# cable_with_five_imu.net
KiCad netlist of a schematic drawn in EAGLE
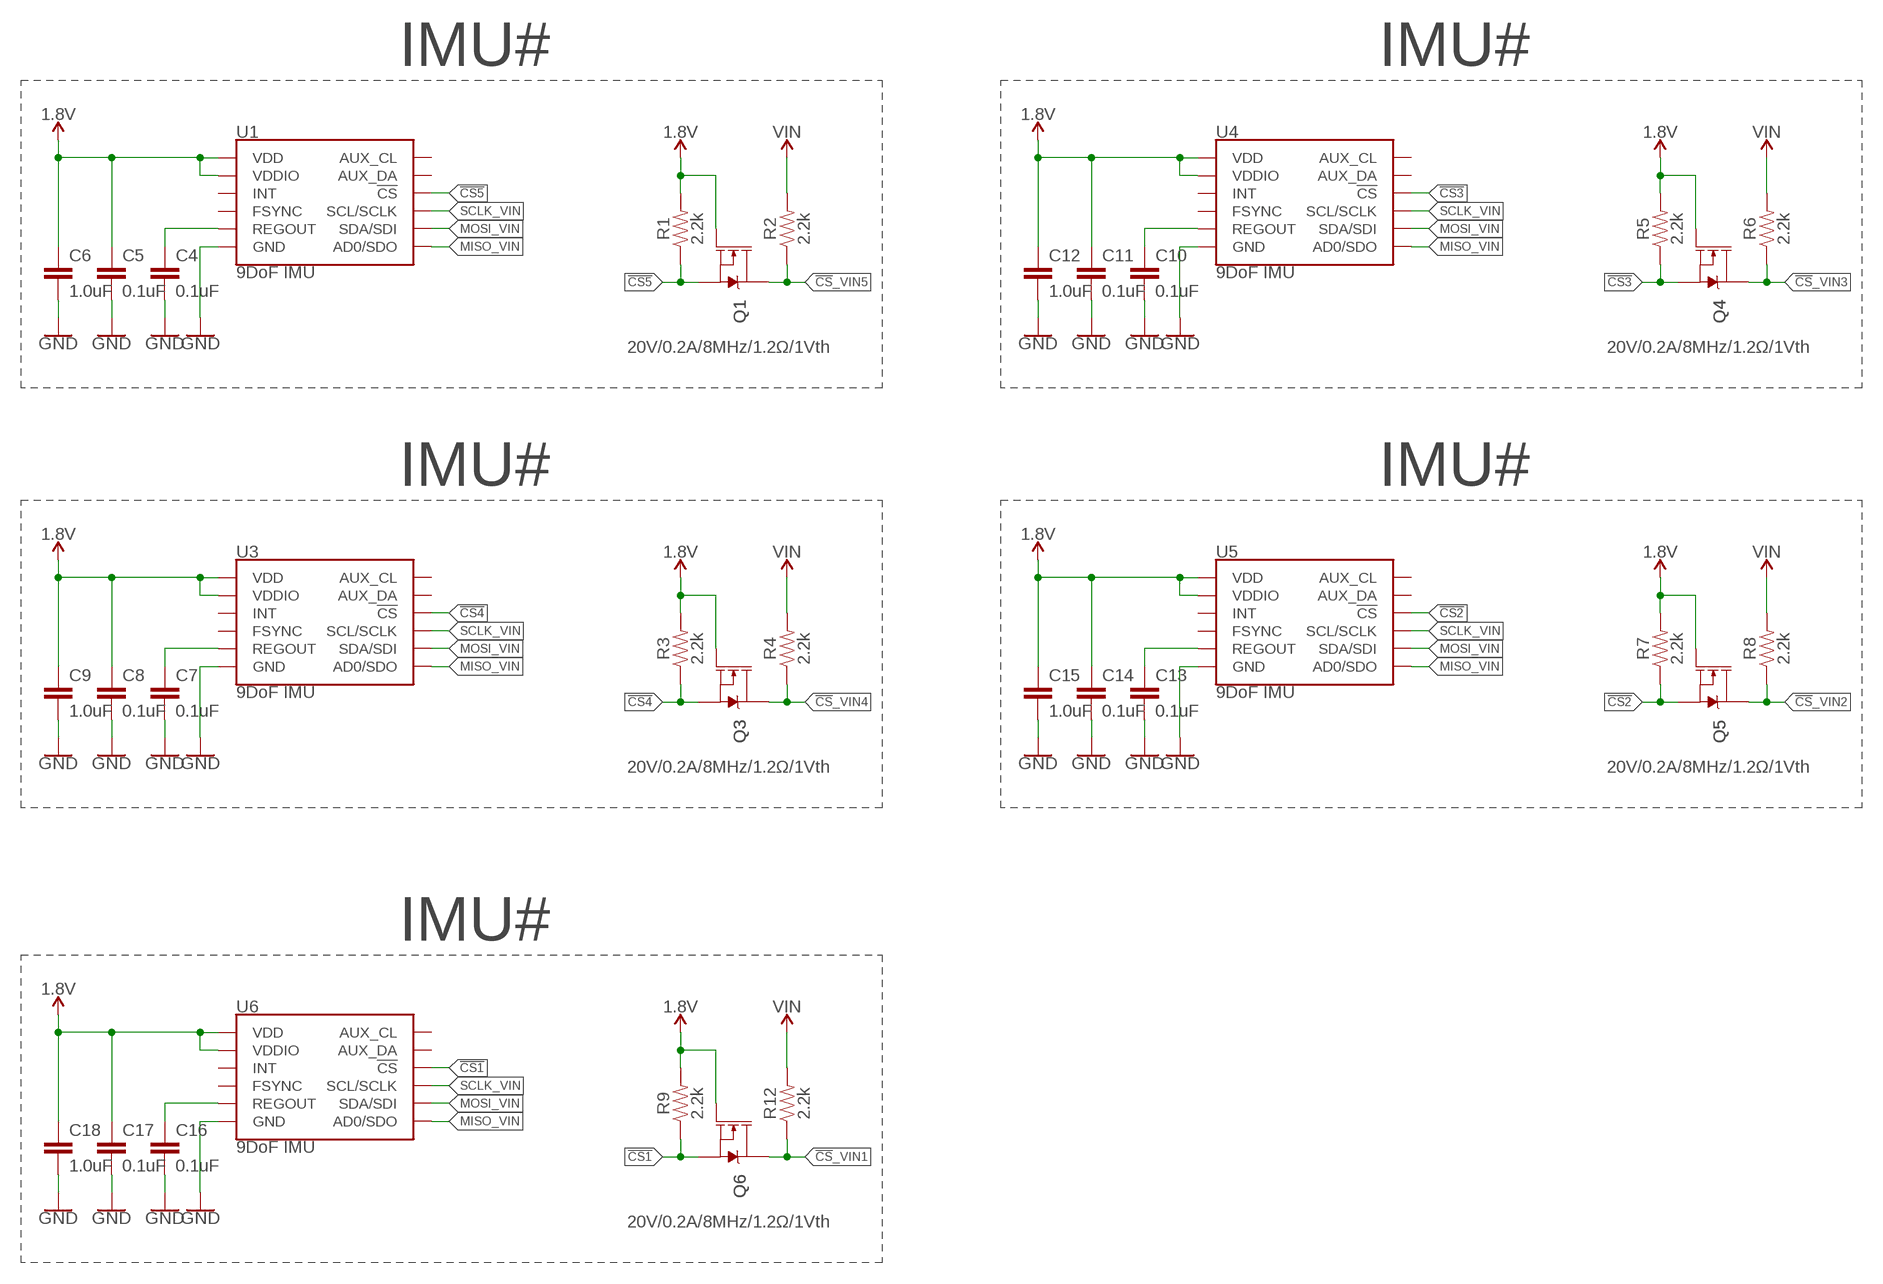
[diagram p0: schematic, sheet 1]

(export (version "E")
  (design (tool "Eeschema 10.0.6"))
  (components
    (comp (ref "C4")
      (value "0.1uF")
      (footprint "eagle-import:0603")
      (libsource (lib "eagle-import") (part "0.1UF-0603-25V-5%"))
    )
    (comp (ref "C5")
      (value "0.1uF")
      (footprint "eagle-import:0603")
      (libsource (lib "eagle-import") (part "0.1UF-0603-25V-5%"))
    )
    (comp (ref "C6")
      (value "1.0uF")
      (footprint "eagle-import:0603")
      (libsource (lib "eagle-import") (part "1.0UF-0603-16V-10%-X7R"))
    )
    (comp (ref "C7")
      (value "0.1uF")
      (footprint "eagle-import:0603")
      (libsource (lib "eagle-import") (part "0.1UF-0603-25V-5%"))
    )
    (comp (ref "C8")
      (value "0.1uF")
      (footprint "eagle-import:0603")
      (libsource (lib "eagle-import") (part "0.1UF-0603-25V-5%"))
    )
    (comp (ref "C9")
      (value "1.0uF")
      (footprint "eagle-import:0603")
      (libsource (lib "eagle-import") (part "1.0UF-0603-16V-10%-X7R"))
    )
    (comp (ref "C10")
      (value "0.1uF")
      (footprint "eagle-import:0603")
      (libsource (lib "eagle-import") (part "0.1UF-0603-25V-5%"))
    )
    (comp (ref "C11")
      (value "0.1uF")
      (footprint "eagle-import:0603")
      (libsource (lib "eagle-import") (part "0.1UF-0603-25V-5%"))
    )
    (comp (ref "C12")
      (value "1.0uF")
      (footprint "eagle-import:0603")
      (libsource (lib "eagle-import") (part "1.0UF-0603-16V-10%-X7R"))
    )
    (comp (ref "C13")
      (value "0.1uF")
      (footprint "eagle-import:0603")
      (libsource (lib "eagle-import") (part "0.1UF-0603-25V-5%"))
    )
    (comp (ref "C14")
      (value "0.1uF")
      (footprint "eagle-import:0603")
      (libsource (lib "eagle-import") (part "0.1UF-0603-25V-5%"))
    )
    (comp (ref "C15")
      (value "1.0uF")
      (footprint "eagle-import:0603")
      (libsource (lib "eagle-import") (part "1.0UF-0603-16V-10%-X7R"))
    )
    (comp (ref "C16")
      (value "0.1uF")
      (footprint "eagle-import:0603")
      (libsource (lib "eagle-import") (part "0.1UF-0603-25V-5%"))
    )
    (comp (ref "C17")
      (value "0.1uF")
      (footprint "eagle-import:0603")
      (libsource (lib "eagle-import") (part "0.1UF-0603-25V-5%"))
    )
    (comp (ref "C18")
      (value "1.0uF")
      (footprint "eagle-import:0603")
      (libsource (lib "eagle-import") (part "1.0UF-0603-16V-10%-X7R"))
    )
    (comp (ref "Q1")
      (value "20V/0.2A/8MHz/1.2Ω/1Vth")
      (footprint "eagle-import:SOT-416FL")
      (libsource (lib "eagle-import") (part "MOSFET-NCH-RE1C002UN"))
    )
    (comp (ref "Q3")
      (value "20V/0.2A/8MHz/1.2Ω/1Vth")
      (footprint "eagle-import:SOT-416FL")
      (libsource (lib "eagle-import") (part "MOSFET-NCH-RE1C002UN"))
    )
    (comp (ref "Q4")
      (value "20V/0.2A/8MHz/1.2Ω/1Vth")
      (footprint "eagle-import:SOT-416FL")
      (libsource (lib "eagle-import") (part "MOSFET-NCH-RE1C002UN"))
    )
    (comp (ref "Q5")
      (value "20V/0.2A/8MHz/1.2Ω/1Vth")
      (footprint "eagle-import:SOT-416FL")
      (libsource (lib "eagle-import") (part "MOSFET-NCH-RE1C002UN"))
    )
    (comp (ref "Q6")
      (value "20V/0.2A/8MHz/1.2Ω/1Vth")
      (footprint "eagle-import:SOT-416FL")
      (libsource (lib "eagle-import") (part "MOSFET-NCH-RE1C002UN"))
    )
    (comp (ref "R1")
      (value "2.2k")
      (footprint "eagle-import:0402-TIGHT")
      (libsource (lib "eagle-import") (part "2.2KOHM-0402T-1/16W-1%"))
    )
    (comp (ref "R2")
      (value "2.2k")
      (footprint "eagle-import:0402-TIGHT")
      (libsource (lib "eagle-import") (part "2.2KOHM-0402T-1/16W-1%"))
    )
    (comp (ref "R3")
      (value "2.2k")
      (footprint "eagle-import:0402-TIGHT")
      (libsource (lib "eagle-import") (part "2.2KOHM-0402T-1/16W-1%"))
    )
    (comp (ref "R4")
      (value "2.2k")
      (footprint "eagle-import:0402-TIGHT")
      (libsource (lib "eagle-import") (part "2.2KOHM-0402T-1/16W-1%"))
    )
    (comp (ref "R5")
      (value "2.2k")
      (footprint "eagle-import:0402-TIGHT")
      (libsource (lib "eagle-import") (part "2.2KOHM-0402T-1/16W-1%"))
    )
    (comp (ref "R6")
      (value "2.2k")
      (footprint "eagle-import:0402-TIGHT")
      (libsource (lib "eagle-import") (part "2.2KOHM-0402T-1/16W-1%"))
    )
    (comp (ref "R7")
      (value "2.2k")
      (footprint "eagle-import:0402-TIGHT")
      (libsource (lib "eagle-import") (part "2.2KOHM-0402T-1/16W-1%"))
    )
    (comp (ref "R8")
      (value "2.2k")
      (footprint "eagle-import:0402-TIGHT")
      (libsource (lib "eagle-import") (part "2.2KOHM-0402T-1/16W-1%"))
    )
    (comp (ref "R9")
      (value "2.2k")
      (footprint "eagle-import:0402-TIGHT")
      (libsource (lib "eagle-import") (part "2.2KOHM-0402T-1/16W-1%"))
    )
    (comp (ref "R12")
      (value "2.2k")
      (footprint "eagle-import:0402-TIGHT")
      (libsource (lib "eagle-import") (part "2.2KOHM-0402T-1/16W-1%"))
    )
    (comp (ref "U1")
      (value "9DoF IMU")
      (footprint "eagle-import:QFN24-3X3")
      (libsource (lib "eagle-import") (part "ICM-20948"))
    )
    (comp (ref "U3")
      (value "9DoF IMU")
      (footprint "eagle-import:QFN24-3X3")
      (libsource (lib "eagle-import") (part "ICM-20948"))
    )
    (comp (ref "U4")
      (value "9DoF IMU")
      (footprint "eagle-import:QFN24-3X3")
      (libsource (lib "eagle-import") (part "ICM-20948"))
    )
    (comp (ref "U5")
      (value "9DoF IMU")
      (footprint "eagle-import:QFN24-3X3")
      (libsource (lib "eagle-import") (part "ICM-20948"))
    )
    (comp (ref "U6")
      (value "9DoF IMU")
      (footprint "eagle-import:QFN24-3X3")
      (libsource (lib "eagle-import") (part "ICM-20948"))
    )
  )
  (nets
    (net (code "1") (name "/~{CS1}") (class "Default")
      (node (ref "Q6") (pin "2") (pinfunction "S_2") (pintype "bidirectional"))
      (node (ref "R9") (pin "1") (pinfunction "1_1") (pintype "passive"))
      (node (ref "U6") (pin "22") (pinfunction "~{CS}_22") (pintype "bidirectional"))
    )
    (net (code "2") (name "/~{CS2}") (class "Default")
      (node (ref "Q5") (pin "2") (pinfunction "S_2") (pintype "bidirectional"))
      (node (ref "R7") (pin "1") (pinfunction "1_1") (pintype "passive"))
      (node (ref "U5") (pin "22") (pinfunction "~{CS}_22") (pintype "bidirectional"))
    )
    (net (code "3") (name "/~{CS3}") (class "Default")
      (node (ref "Q4") (pin "2") (pinfunction "S_2") (pintype "bidirectional"))
      (node (ref "R5") (pin "1") (pinfunction "1_1") (pintype "passive"))
      (node (ref "U4") (pin "22") (pinfunction "~{CS}_22") (pintype "bidirectional"))
    )
    (net (code "4") (name "/~{CS4}") (class "Default")
      (node (ref "Q3") (pin "2") (pinfunction "S_2") (pintype "bidirectional"))
      (node (ref "R3") (pin "1") (pinfunction "1_1") (pintype "passive"))
      (node (ref "U3") (pin "22") (pinfunction "~{CS}_22") (pintype "bidirectional"))
    )
    (net (code "5") (name "/~{CS5}") (class "Default")
      (node (ref "Q1") (pin "2") (pinfunction "S_2") (pintype "bidirectional"))
      (node (ref "R1") (pin "1") (pinfunction "1_1") (pintype "passive"))
      (node (ref "U1") (pin "22") (pinfunction "~{CS}_22") (pintype "bidirectional"))
    )
    (net (code "6") (name "/~{CS}_VIN1") (class "Default")
      (node (ref "Q6") (pin "3") (pinfunction "D_3") (pintype "bidirectional"))
      (node (ref "R12") (pin "1") (pinfunction "1_1") (pintype "passive"))
    )
    (net (code "7") (name "/~{CS}_VIN2") (class "Default")
      (node (ref "Q5") (pin "3") (pinfunction "D_3") (pintype "bidirectional"))
      (node (ref "R8") (pin "1") (pinfunction "1_1") (pintype "passive"))
    )
    (net (code "8") (name "/~{CS}_VIN3") (class "Default")
      (node (ref "Q4") (pin "3") (pinfunction "D_3") (pintype "bidirectional"))
      (node (ref "R6") (pin "1") (pinfunction "1_1") (pintype "passive"))
    )
    (net (code "9") (name "/~{CS}_VIN4") (class "Default")
      (node (ref "Q3") (pin "3") (pinfunction "D_3") (pintype "bidirectional"))
      (node (ref "R4") (pin "1") (pinfunction "1_1") (pintype "passive"))
    )
    (net (code "10") (name "/~{CS}_VIN5") (class "Default")
      (node (ref "Q1") (pin "3") (pinfunction "D_3") (pintype "bidirectional"))
      (node (ref "R2") (pin "1") (pinfunction "1_1") (pintype "passive"))
    )
    (net (code "11") (name "1.8V") (class "Default")
      (node (ref "C11") (pin "1") (pinfunction "1_1") (pintype "passive"))
      (node (ref "C12") (pin "1") (pinfunction "1_1") (pintype "passive"))
      (node (ref "C14") (pin "1") (pinfunction "1_1") (pintype "passive"))
      (node (ref "C15") (pin "1") (pinfunction "1_1") (pintype "passive"))
      (node (ref "C17") (pin "1") (pinfunction "1_1") (pintype "passive"))
      (node (ref "C18") (pin "1") (pinfunction "1_1") (pintype "passive"))
      (node (ref "C5") (pin "1") (pinfunction "1_1") (pintype "passive"))
      (node (ref "C6") (pin "1") (pinfunction "1_1") (pintype "passive"))
      (node (ref "C8") (pin "1") (pinfunction "1_1") (pintype "passive"))
      (node (ref "C9") (pin "1") (pinfunction "1_1") (pintype "passive"))
      (node (ref "Q1") (pin "1") (pinfunction "G_1") (pintype "bidirectional"))
      (node (ref "Q3") (pin "1") (pinfunction "G_1") (pintype "bidirectional"))
      (node (ref "Q4") (pin "1") (pinfunction "G_1") (pintype "bidirectional"))
      (node (ref "Q5") (pin "1") (pinfunction "G_1") (pintype "bidirectional"))
      (node (ref "Q6") (pin "1") (pinfunction "G_1") (pintype "bidirectional"))
      (node (ref "R1") (pin "2") (pinfunction "2_2") (pintype "passive"))
      (node (ref "R3") (pin "2") (pinfunction "2_2") (pintype "passive"))
      (node (ref "R5") (pin "2") (pinfunction "2_2") (pintype "passive"))
      (node (ref "R7") (pin "2") (pinfunction "2_2") (pintype "passive"))
      (node (ref "R9") (pin "2") (pinfunction "2_2") (pintype "passive"))
      (node (ref "U1") (pin "13") (pinfunction "VDD_13") (pintype "bidirectional"))
      (node (ref "U1") (pin "8") (pinfunction "VDDIO_8") (pintype "bidirectional"))
      (node (ref "U3") (pin "13") (pinfunction "VDD_13") (pintype "bidirectional"))
      (node (ref "U3") (pin "8") (pinfunction "VDDIO_8") (pintype "bidirectional"))
      (node (ref "U4") (pin "13") (pinfunction "VDD_13") (pintype "bidirectional"))
      (node (ref "U4") (pin "8") (pinfunction "VDDIO_8") (pintype "bidirectional"))
      (node (ref "U5") (pin "13") (pinfunction "VDD_13") (pintype "bidirectional"))
      (node (ref "U5") (pin "8") (pinfunction "VDDIO_8") (pintype "bidirectional"))
      (node (ref "U6") (pin "13") (pinfunction "VDD_13") (pintype "bidirectional"))
      (node (ref "U6") (pin "8") (pinfunction "VDDIO_8") (pintype "bidirectional"))
    )
    (net (code "12") (name "GND") (class "Default")
      (node (ref "C10") (pin "2") (pinfunction "2_2") (pintype "passive"))
      (node (ref "C11") (pin "2") (pinfunction "2_2") (pintype "passive"))
      (node (ref "C12") (pin "2") (pinfunction "2_2") (pintype "passive"))
      (node (ref "C13") (pin "2") (pinfunction "2_2") (pintype "passive"))
      (node (ref "C14") (pin "2") (pinfunction "2_2") (pintype "passive"))
      (node (ref "C15") (pin "2") (pinfunction "2_2") (pintype "passive"))
      (node (ref "C16") (pin "2") (pinfunction "2_2") (pintype "passive"))
      (node (ref "C17") (pin "2") (pinfunction "2_2") (pintype "passive"))
      (node (ref "C18") (pin "2") (pinfunction "2_2") (pintype "passive"))
      (node (ref "C4") (pin "2") (pinfunction "2_2") (pintype "passive"))
      (node (ref "C5") (pin "2") (pinfunction "2_2") (pintype "passive"))
      (node (ref "C6") (pin "2") (pinfunction "2_2") (pintype "passive"))
      (node (ref "C7") (pin "2") (pinfunction "2_2") (pintype "passive"))
      (node (ref "C8") (pin "2") (pinfunction "2_2") (pintype "passive"))
      (node (ref "C9") (pin "2") (pinfunction "2_2") (pintype "passive"))
      (node (ref "U1") (pin "18") (pinfunction "GND_18") (pintype "bidirectional"))
      (node (ref "U1") (pin "20") (pinfunction "GND_20") (pintype "bidirectional"))
      (node (ref "U3") (pin "18") (pinfunction "GND_18") (pintype "bidirectional"))
      (node (ref "U3") (pin "20") (pinfunction "GND_20") (pintype "bidirectional"))
      (node (ref "U4") (pin "18") (pinfunction "GND_18") (pintype "bidirectional"))
      (node (ref "U4") (pin "20") (pinfunction "GND_20") (pintype "bidirectional"))
      (node (ref "U5") (pin "18") (pinfunction "GND_18") (pintype "bidirectional"))
      (node (ref "U5") (pin "20") (pinfunction "GND_20") (pintype "bidirectional"))
      (node (ref "U6") (pin "18") (pinfunction "GND_18") (pintype "bidirectional"))
      (node (ref "U6") (pin "20") (pinfunction "GND_20") (pintype "bidirectional"))
    )
    (net (code "13") (name "MISO_VIN") (class "Default")
      (node (ref "U1") (pin "9") (pinfunction "AD0/SDO_9") (pintype "bidirectional"))
      (node (ref "U3") (pin "9") (pinfunction "AD0/SDO_9") (pintype "bidirectional"))
      (node (ref "U4") (pin "9") (pinfunction "AD0/SDO_9") (pintype "bidirectional"))
      (node (ref "U5") (pin "9") (pinfunction "AD0/SDO_9") (pintype "bidirectional"))
      (node (ref "U6") (pin "9") (pinfunction "AD0/SDO_9") (pintype "bidirectional"))
    )
    (net (code "14") (name "MOSI_VIN") (class "Default")
      (node (ref "U1") (pin "24") (pinfunction "SDA/SDI_24") (pintype "bidirectional"))
      (node (ref "U3") (pin "24") (pinfunction "SDA/SDI_24") (pintype "bidirectional"))
      (node (ref "U4") (pin "24") (pinfunction "SDA/SDI_24") (pintype "bidirectional"))
      (node (ref "U5") (pin "24") (pinfunction "SDA/SDI_24") (pintype "bidirectional"))
      (node (ref "U6") (pin "24") (pinfunction "SDA/SDI_24") (pintype "bidirectional"))
    )
    (net (code "15") (name "Net-(U1-REGOUT)") (class "Default")
      (node (ref "C4") (pin "1") (pinfunction "1_1") (pintype "passive"))
      (node (ref "U1") (pin "10") (pinfunction "REGOUT_10") (pintype "bidirectional"))
    )
    (net (code "16") (name "Net-(U3-REGOUT)") (class "Default")
      (node (ref "C7") (pin "1") (pinfunction "1_1") (pintype "passive"))
      (node (ref "U3") (pin "10") (pinfunction "REGOUT_10") (pintype "bidirectional"))
    )
    (net (code "17") (name "Net-(U4-REGOUT)") (class "Default")
      (node (ref "C10") (pin "1") (pinfunction "1_1") (pintype "passive"))
      (node (ref "U4") (pin "10") (pinfunction "REGOUT_10") (pintype "bidirectional"))
    )
    (net (code "18") (name "Net-(U5-REGOUT)") (class "Default")
      (node (ref "C13") (pin "1") (pinfunction "1_1") (pintype "passive"))
      (node (ref "U5") (pin "10") (pinfunction "REGOUT_10") (pintype "bidirectional"))
    )
    (net (code "19") (name "Net-(U6-REGOUT)") (class "Default")
      (node (ref "C16") (pin "1") (pinfunction "1_1") (pintype "passive"))
      (node (ref "U6") (pin "10") (pinfunction "REGOUT_10") (pintype "bidirectional"))
    )
    (net (code "20") (name "SCLK_VIN") (class "Default")
      (node (ref "U1") (pin "23") (pinfunction "SCL/SCLK_23") (pintype "bidirectional"))
      (node (ref "U3") (pin "23") (pinfunction "SCL/SCLK_23") (pintype "bidirectional"))
      (node (ref "U4") (pin "23") (pinfunction "SCL/SCLK_23") (pintype "bidirectional"))
      (node (ref "U5") (pin "23") (pinfunction "SCL/SCLK_23") (pintype "bidirectional"))
      (node (ref "U6") (pin "23") (pinfunction "SCL/SCLK_23") (pintype "bidirectional"))
    )
    (net (code "21") (name "VIN") (class "Default")
      (node (ref "R12") (pin "2") (pinfunction "2_2") (pintype "passive"))
      (node (ref "R2") (pin "2") (pinfunction "2_2") (pintype "passive"))
      (node (ref "R4") (pin "2") (pinfunction "2_2") (pintype "passive"))
      (node (ref "R6") (pin "2") (pinfunction "2_2") (pintype "passive"))
      (node (ref "R8") (pin "2") (pinfunction "2_2") (pintype "passive"))
    )
    (net (code "22") (name "unconnected-(U1-AUX_CL-Pad7)") (class "Default")
      (node (ref "U1") (pin "7") (pinfunction "AUX_CL_7") (pintype "bidirectional"))
    )
    (net (code "23") (name "unconnected-(U1-AUX_DA-Pad21)") (class "Default")
      (node (ref "U1") (pin "21") (pinfunction "AUX_DA_21") (pintype "bidirectional"))
    )
    (net (code "24") (name "unconnected-(U1-FSYNC-Pad11)") (class "Default")
      (node (ref "U1") (pin "11") (pinfunction "FSYNC_11") (pintype "bidirectional"))
    )
    (net (code "25") (name "unconnected-(U1-INT-Pad12)") (class "Default")
      (node (ref "U1") (pin "12") (pinfunction "INT_12") (pintype "bidirectional"))
    )
    (net (code "26") (name "unconnected-(U3-AUX_CL-Pad7)") (class "Default")
      (node (ref "U3") (pin "7") (pinfunction "AUX_CL_7") (pintype "bidirectional"))
    )
    (net (code "27") (name "unconnected-(U3-AUX_DA-Pad21)") (class "Default")
      (node (ref "U3") (pin "21") (pinfunction "AUX_DA_21") (pintype "bidirectional"))
    )
    (net (code "28") (name "unconnected-(U3-FSYNC-Pad11)") (class "Default")
      (node (ref "U3") (pin "11") (pinfunction "FSYNC_11") (pintype "bidirectional"))
    )
    (net (code "29") (name "unconnected-(U3-INT-Pad12)") (class "Default")
      (node (ref "U3") (pin "12") (pinfunction "INT_12") (pintype "bidirectional"))
    )
    (net (code "30") (name "unconnected-(U4-AUX_CL-Pad7)") (class "Default")
      (node (ref "U4") (pin "7") (pinfunction "AUX_CL_7") (pintype "bidirectional"))
    )
    (net (code "31") (name "unconnected-(U4-AUX_DA-Pad21)") (class "Default")
      (node (ref "U4") (pin "21") (pinfunction "AUX_DA_21") (pintype "bidirectional"))
    )
    (net (code "32") (name "unconnected-(U4-FSYNC-Pad11)") (class "Default")
      (node (ref "U4") (pin "11") (pinfunction "FSYNC_11") (pintype "bidirectional"))
    )
    (net (code "33") (name "unconnected-(U4-INT-Pad12)") (class "Default")
      (node (ref "U4") (pin "12") (pinfunction "INT_12") (pintype "bidirectional"))
    )
    (net (code "34") (name "unconnected-(U5-AUX_CL-Pad7)") (class "Default")
      (node (ref "U5") (pin "7") (pinfunction "AUX_CL_7") (pintype "bidirectional"))
    )
    (net (code "35") (name "unconnected-(U5-AUX_DA-Pad21)") (class "Default")
      (node (ref "U5") (pin "21") (pinfunction "AUX_DA_21") (pintype "bidirectional"))
    )
    (net (code "36") (name "unconnected-(U5-FSYNC-Pad11)") (class "Default")
      (node (ref "U5") (pin "11") (pinfunction "FSYNC_11") (pintype "bidirectional"))
    )
    (net (code "37") (name "unconnected-(U5-INT-Pad12)") (class "Default")
      (node (ref "U5") (pin "12") (pinfunction "INT_12") (pintype "bidirectional"))
    )
    (net (code "38") (name "unconnected-(U6-AUX_CL-Pad7)") (class "Default")
      (node (ref "U6") (pin "7") (pinfunction "AUX_CL_7") (pintype "bidirectional"))
    )
    (net (code "39") (name "unconnected-(U6-AUX_DA-Pad21)") (class "Default")
      (node (ref "U6") (pin "21") (pinfunction "AUX_DA_21") (pintype "bidirectional"))
    )
    (net (code "40") (name "unconnected-(U6-FSYNC-Pad11)") (class "Default")
      (node (ref "U6") (pin "11") (pinfunction "FSYNC_11") (pintype "bidirectional"))
    )
    (net (code "41") (name "unconnected-(U6-INT-Pad12)") (class "Default")
      (node (ref "U6") (pin "12") (pinfunction "INT_12") (pintype "bidirectional"))
    )
  )
)
